# arduino.net
KiCad netlist of a schematic drawn in EAGLE
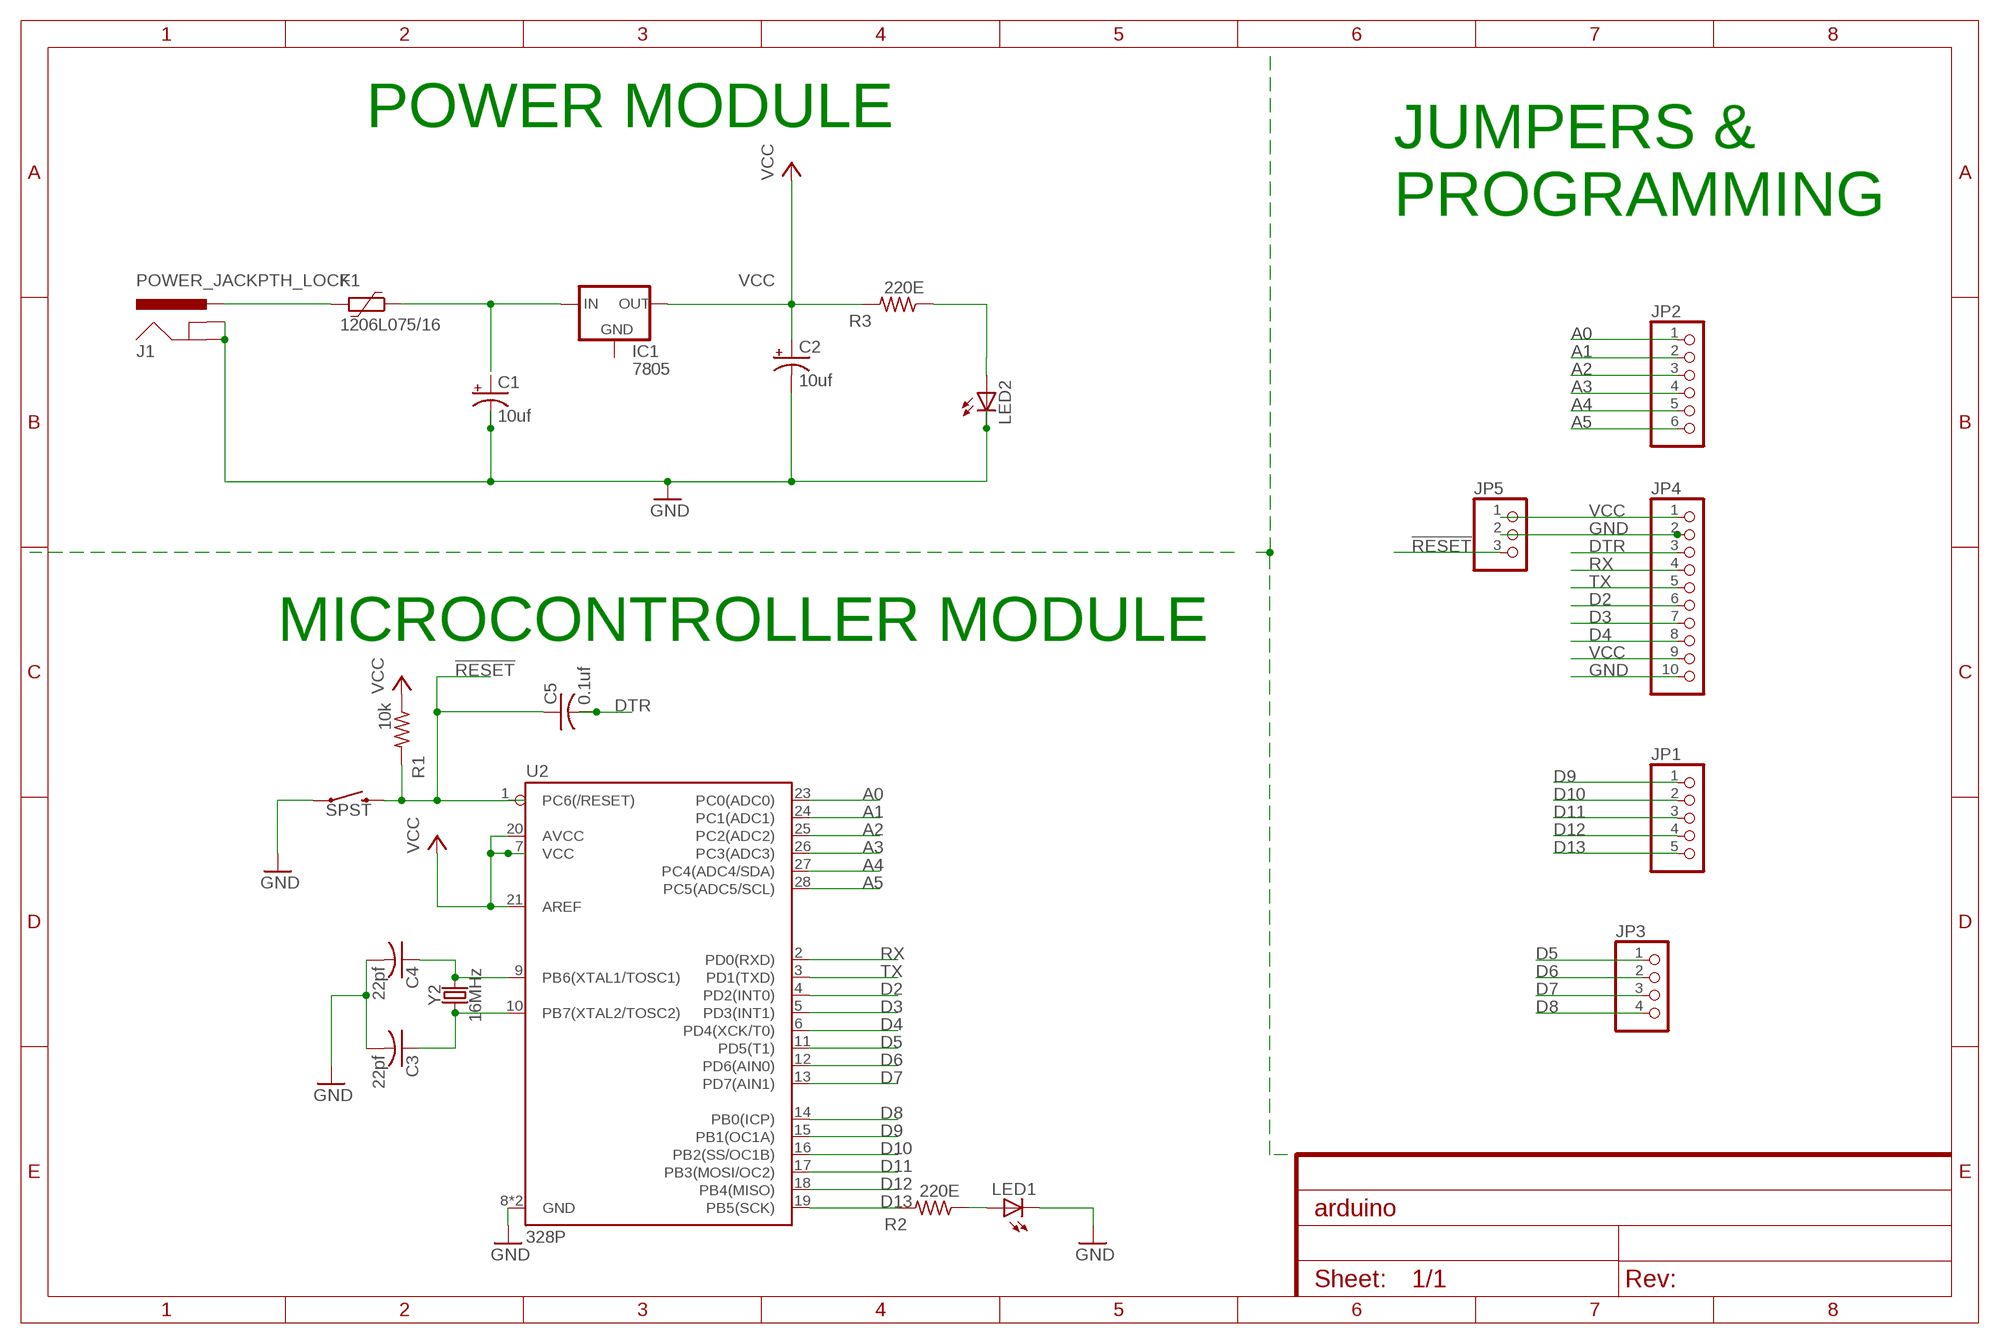
[diagram p0: schematic, sheet 1]

(export (version "E")
  (design (tool "Eeschema 10.0.6"))
  (components
    (comp (ref "C1")
      (value "10uf")
      (footprint "eagle-import:E2,5-6E")
      (libsource (lib "eagle-import") (part "CPOL-USE2,5-6E"))
    )
    (comp (ref "C2")
      (value "10uf")
      (footprint "eagle-import:E2,5-6E")
      (libsource (lib "eagle-import") (part "CPOL-USE2,5-6E"))
    )
    (comp (ref "C3")
      (value "22pf")
      (footprint "eagle-import:C025-024X044")
      (libsource (lib "eagle-import") (part "C-US025-024X044"))
    )
    (comp (ref "C4")
      (value "22pf")
      (footprint "eagle-import:C025-024X044")
      (libsource (lib "eagle-import") (part "C-US025-024X044"))
    )
    (comp (ref "C5")
      (value "0.1uf")
      (footprint "eagle-import:C025-024X044")
      (libsource (lib "eagle-import") (part "C-US025-024X044"))
    )
    (comp (ref "F1")
      (value "1206L075/16")
      (footprint "eagle-import:1206L")
      (fields (field (name "MF") "Littelfuse"))
      (libsource (lib "eagle-import") (part "?1206L075/16"))
    )
    (comp (ref "IC1")
      (value "7805")
      (footprint "eagle-import:78XXS")
      (libsource (lib "eagle-import") (part "78XXS"))
    )
    (comp (ref "J1")
      (value "POWER_JACKPTH_LOCK")
      (footprint "eagle-import:POWER_JACK_PTH_LOCK")
      (libsource (lib "eagle-import") (part "POWER_JACKPTH_LOCK"))
    )
    (comp (ref "JP1")
      (value "PINHD-1X5")
      (footprint "eagle-import:1X05")
      (libsource (lib "eagle-import") (part "PINHD-1X5"))
    )
    (comp (ref "JP2")
      (value "PINHD-1X6")
      (footprint "eagle-import:1X06")
      (libsource (lib "eagle-import") (part "PINHD-1X6"))
    )
    (comp (ref "JP3")
      (value "PINHD-1X4")
      (footprint "eagle-import:1X04")
      (libsource (lib "eagle-import") (part "PINHD-1X4"))
    )
    (comp (ref "JP4")
      (value "PINHD-1X10")
      (footprint "eagle-import:1X10")
      (libsource (lib "eagle-import") (part "PINHD-1X10"))
    )
    (comp (ref "JP5")
      (value "PINHD-1X3")
      (footprint "eagle-import:1X03")
      (libsource (lib "eagle-import") (part "PINHD-1X3"))
    )
    (comp (ref "LED1")
      (value "LED3MM")
      (footprint "eagle-import:LED3MM")
      (libsource (lib "eagle-import") (part "LED3MM"))
    )
    (comp (ref "LED2")
      (value "LED3MM")
      (footprint "eagle-import:LED3MM")
      (libsource (lib "eagle-import") (part "LED3MM"))
    )
    (comp (ref "R1")
      (value "10k")
      (footprint "eagle-import:0204_7")
      (libsource (lib "eagle-import") (part "R-US_0204/7"))
    )
    (comp (ref "R2")
      (value "220E")
      (footprint "eagle-import:0204_7")
      (libsource (lib "eagle-import") (part "R-US_0204/7"))
    )
    (comp (ref "R3")
      (value "220E")
      (footprint "eagle-import:0204_7")
      (libsource (lib "eagle-import") (part "R-US_0204/7"))
    )
    (comp (ref "S2")
      (value "SPST")
      (footprint "eagle-import:TACTILE_SWITCH_PTH_6.0MM")
      (libsource (lib "eagle-import") (part "MOMENTARY-SWITCH-SPST-PTH-6.0MM"))
    )
    (comp (ref "U2")
      (value "328P")
      (footprint "eagle-import:DIP28")
      (libsource (lib "eagle-import") (part "ATMEGA328P_PDIP"))
    )
    (comp (ref "Y2")
      (value "16MHz")
      (footprint "eagle-import:HC49US")
      (libsource (lib "eagle-import") (part "CRYSTAL-16MHZPTH-HC49US"))
    )
  )
  (nets
    (net (code "1") (name "/A0") (class "Default")
      (node (ref "JP2") (pin "1") (pinfunction "1_1") (pintype "passive"))
      (node (ref "U2") (pin "23") (pinfunction "PC0(ADC0)_23") (pintype "bidirectional"))
    )
    (net (code "2") (name "/A1") (class "Default")
      (node (ref "JP2") (pin "2") (pinfunction "2_2") (pintype "passive"))
      (node (ref "U2") (pin "24") (pinfunction "PC1(ADC1)_24") (pintype "bidirectional"))
    )
    (net (code "3") (name "/A2") (class "Default")
      (node (ref "JP2") (pin "3") (pinfunction "3_3") (pintype "passive"))
      (node (ref "U2") (pin "25") (pinfunction "PC2(ADC2)_25") (pintype "bidirectional"))
    )
    (net (code "4") (name "/A3") (class "Default")
      (node (ref "JP2") (pin "4") (pinfunction "4_4") (pintype "passive"))
      (node (ref "U2") (pin "26") (pinfunction "PC3(ADC3)_26") (pintype "bidirectional"))
    )
    (net (code "5") (name "/A4") (class "Default")
      (node (ref "JP2") (pin "5") (pinfunction "5_5") (pintype "passive"))
      (node (ref "U2") (pin "27") (pinfunction "PC4(ADC4/SDA)_27") (pintype "bidirectional"))
    )
    (net (code "6") (name "/A5") (class "Default")
      (node (ref "JP2") (pin "6") (pinfunction "6_6") (pintype "passive"))
      (node (ref "U2") (pin "28") (pinfunction "PC5(ADC5/SCL)_28") (pintype "bidirectional"))
    )
    (net (code "7") (name "/D2") (class "Default")
      (node (ref "JP4") (pin "6") (pinfunction "6_6") (pintype "passive"))
      (node (ref "U2") (pin "4") (pinfunction "PD2(INT0)_4") (pintype "bidirectional"))
    )
    (net (code "8") (name "/D3") (class "Default")
      (node (ref "JP4") (pin "7") (pinfunction "7_7") (pintype "passive"))
      (node (ref "U2") (pin "5") (pinfunction "PD3(INT1)_5") (pintype "bidirectional"))
    )
    (net (code "9") (name "/D4") (class "Default")
      (node (ref "JP4") (pin "8") (pinfunction "8_8") (pintype "passive"))
      (node (ref "U2") (pin "6") (pinfunction "PD4(XCK/T0)_6") (pintype "bidirectional"))
    )
    (net (code "10") (name "/D5") (class "Default")
      (node (ref "JP3") (pin "1") (pinfunction "1_1") (pintype "passive"))
      (node (ref "U2") (pin "11") (pinfunction "PD5(T1)_11") (pintype "bidirectional"))
    )
    (net (code "11") (name "/D6") (class "Default")
      (node (ref "JP3") (pin "2") (pinfunction "2_2") (pintype "passive"))
      (node (ref "U2") (pin "12") (pinfunction "PD6(AIN0)_12") (pintype "bidirectional"))
    )
    (net (code "12") (name "/D7") (class "Default")
      (node (ref "JP3") (pin "3") (pinfunction "3_3") (pintype "passive"))
      (node (ref "U2") (pin "13") (pinfunction "PD7(AIN1)_13") (pintype "bidirectional"))
    )
    (net (code "13") (name "/D8") (class "Default")
      (node (ref "JP3") (pin "4") (pinfunction "4_4") (pintype "passive"))
      (node (ref "U2") (pin "14") (pinfunction "PB0(ICP)_14") (pintype "bidirectional"))
    )
    (net (code "14") (name "/D9") (class "Default")
      (node (ref "JP1") (pin "1") (pinfunction "1_1") (pintype "passive"))
      (node (ref "U2") (pin "15") (pinfunction "PB1(OC1A)_15") (pintype "bidirectional"))
    )
    (net (code "15") (name "/D10") (class "Default")
      (node (ref "JP1") (pin "2") (pinfunction "2_2") (pintype "passive"))
      (node (ref "U2") (pin "16") (pinfunction "PB2(SS/OC1B)_16") (pintype "bidirectional"))
    )
    (net (code "16") (name "/D11") (class "Default")
      (node (ref "JP1") (pin "3") (pinfunction "3_3") (pintype "passive"))
      (node (ref "U2") (pin "17") (pinfunction "PB3(MOSI/OC2)_17") (pintype "bidirectional"))
    )
    (net (code "17") (name "/D12") (class "Default")
      (node (ref "JP1") (pin "4") (pinfunction "4_4") (pintype "passive"))
      (node (ref "U2") (pin "18") (pinfunction "PB4(MISO)_18") (pintype "bidirectional"))
    )
    (net (code "18") (name "/D13") (class "Default")
      (node (ref "JP1") (pin "5") (pinfunction "5_5") (pintype "passive"))
      (node (ref "R2") (pin "2") (pinfunction "2_2") (pintype "passive"))
      (node (ref "U2") (pin "19") (pinfunction "PB5(SCK)_19") (pintype "bidirectional"))
    )
    (net (code "19") (name "/DTR") (class "Default")
      (node (ref "C5") (pin "2") (pinfunction "2_2") (pintype "passive"))
      (node (ref "JP4") (pin "3") (pinfunction "3_3") (pintype "passive"))
    )
    (net (code "20") (name "/RX") (class "Default")
      (node (ref "JP4") (pin "4") (pinfunction "4_4") (pintype "passive"))
      (node (ref "U2") (pin "2") (pinfunction "PD0(RXD)_2") (pintype "bidirectional"))
    )
    (net (code "21") (name "/TX") (class "Default")
      (node (ref "JP4") (pin "5") (pinfunction "5_5") (pintype "passive"))
      (node (ref "U2") (pin "3") (pinfunction "PD1(TXD)_3") (pintype "bidirectional"))
    )
    (net (code "22") (name "/~{RESET}") (class "Default")
      (node (ref "C5") (pin "1") (pinfunction "1_1") (pintype "passive"))
      (node (ref "JP5") (pin "3") (pinfunction "3_3") (pintype "passive"))
      (node (ref "R1") (pin "2") (pinfunction "2_2") (pintype "passive"))
      (node (ref "S2") (pin "3") (pinfunction "2_3") (pintype "passive"))
      (node (ref "U2") (pin "1") (pinfunction "PC6(/RESET)_1") (pintype "bidirectional"))
    )
    (net (code "23") (name "GND") (class "Default")
      (node (ref "C1") (pin "-") (pinfunction "-_-") (pintype "passive"))
      (node (ref "C2") (pin "-") (pinfunction "-_-") (pintype "passive"))
      (node (ref "C3") (pin "2") (pinfunction "2_2") (pintype "passive"))
      (node (ref "C4") (pin "2") (pinfunction "2_2") (pintype "passive"))
      (node (ref "J1") (pin "GND") (pinfunction "GND_GND") (pintype "bidirectional"))
      (node (ref "J1") (pin "GNDBREAK") (pinfunction "GNDBREAK_GNDBREAK") (pintype "bidirectional"))
      (node (ref "JP4") (pin "10") (pinfunction "10_10") (pintype "passive"))
      (node (ref "JP4") (pin "2") (pinfunction "2_2") (pintype "passive"))
      (node (ref "JP5") (pin "2") (pinfunction "2_2") (pintype "passive"))
      (node (ref "LED1") (pin "K") (pinfunction "C_K") (pintype "passive"))
      (node (ref "LED2") (pin "K") (pinfunction "C_K") (pintype "passive"))
      (node (ref "S2") (pin "1") (pinfunction "1_1") (pintype "passive"))
      (node (ref "U2") (pin "22") (pinfunction "GND_22") (pintype "bidirectional"))
      (node (ref "U2") (pin "8") (pinfunction "GND_8") (pintype "bidirectional"))
    )
    (net (code "24") (name "Net-(C1-Pad+)") (class "Default")
      (node (ref "C1") (pin "+") (pinfunction "+_+") (pintype "passive"))
      (node (ref "F1") (pin "1") (pinfunction "1_1") (pintype "passive"))
      (node (ref "IC1") (pin "IN") (pinfunction "IN_IN") (pintype "input"))
    )
    (net (code "25") (name "Net-(F1-Pad2)") (class "Default")
      (node (ref "F1") (pin "2") (pinfunction "2_2") (pintype "passive"))
      (node (ref "J1") (pin "PWR") (pinfunction "PWR_PWR") (pintype "bidirectional"))
    )
    (net (code "26") (name "Net-(LED1-PadA)") (class "Default")
      (node (ref "LED1") (pin "A") (pinfunction "A_A") (pintype "passive"))
      (node (ref "R2") (pin "1") (pinfunction "1_1") (pintype "passive"))
    )
    (net (code "27") (name "Net-(LED2-PadA)") (class "Default")
      (node (ref "LED2") (pin "A") (pinfunction "A_A") (pintype "passive"))
      (node (ref "R3") (pin "1") (pinfunction "1_1") (pintype "passive"))
    )
    (net (code "28") (name "Net-(U2-PB6(XTAL1{slash}TOSC1))") (class "Default")
      (node (ref "C4") (pin "1") (pinfunction "1_1") (pintype "passive"))
      (node (ref "U2") (pin "9") (pinfunction "PB6(XTAL1/TOSC1)_9") (pintype "bidirectional"))
      (node (ref "Y2") (pin "2") (pinfunction "2_2") (pintype "passive"))
    )
    (net (code "29") (name "Net-(U2-PB7(XTAL2{slash}TOSC2))") (class "Default")
      (node (ref "C3") (pin "1") (pinfunction "1_1") (pintype "passive"))
      (node (ref "U2") (pin "10") (pinfunction "PB7(XTAL2/TOSC2)_10") (pintype "bidirectional"))
      (node (ref "Y2") (pin "1") (pinfunction "1_1") (pintype "passive"))
    )
    (net (code "30") (name "VCC") (class "Default")
      (node (ref "C2") (pin "+") (pinfunction "+_+") (pintype "passive"))
      (node (ref "IC1") (pin "OUT") (pinfunction "OUT_OUT") (pintype "passive"))
      (node (ref "JP4") (pin "1") (pinfunction "1_1") (pintype "passive"))
      (node (ref "JP4") (pin "9") (pinfunction "9_9") (pintype "passive"))
      (node (ref "JP5") (pin "1") (pinfunction "1_1") (pintype "passive"))
      (node (ref "R1") (pin "1") (pinfunction "1_1") (pintype "passive"))
      (node (ref "R3") (pin "2") (pinfunction "2_2") (pintype "passive"))
      (node (ref "U2") (pin "20") (pinfunction "AVCC_20") (pintype "bidirectional"))
      (node (ref "U2") (pin "21") (pinfunction "AREF_21") (pintype "bidirectional"))
      (node (ref "U2") (pin "7") (pinfunction "VCC_7") (pintype "bidirectional"))
    )
    (net (code "31") (name "unconnected-(IC1-PadGND)") (class "Default")
      (node (ref "IC1") (pin "GND") (pinfunction "GND_GND") (pintype "input"))
    )
  )
)
